# Sensors.net
KiCad netlist of a schematic drawn in Altium Designer
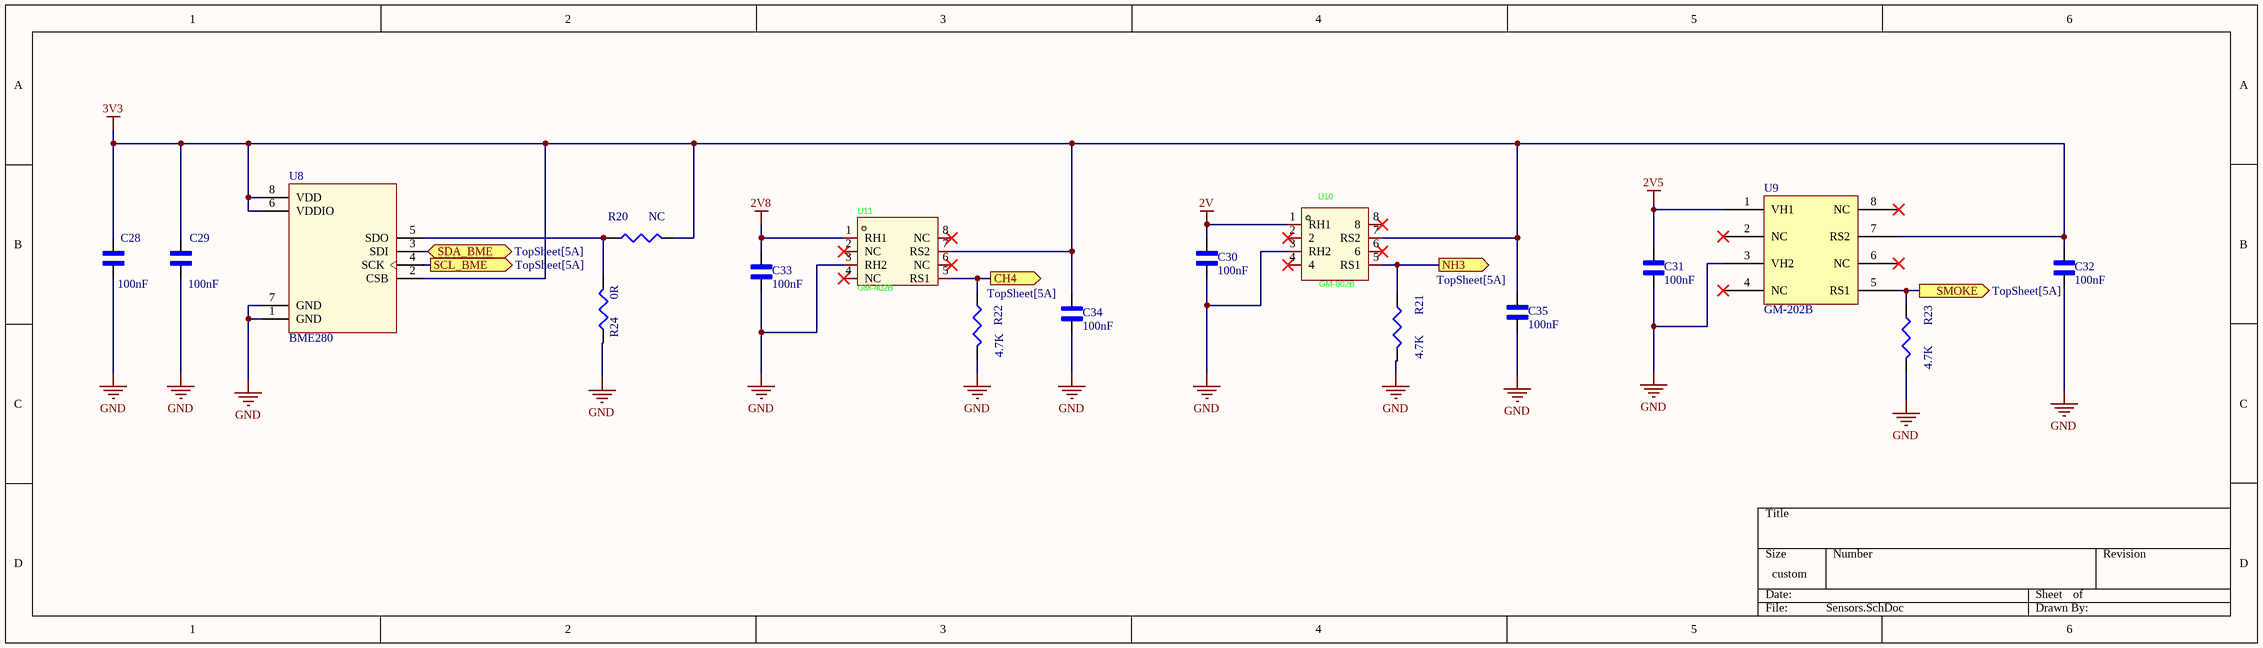
[diagram p0: Sensors.SchDoc]

(export (version "E")
  (design (tool "Eeschema 10.0.6"))
  (components
    (comp (ref "C28")
      (value "100nF")
      (footprint "C0603")
      (fields (field (name "MF") "Murata") (field (name "MP") "GJM1555C1HR10BB01J"))
      (libsource (lib "common component") (part "Capacitor non polar"))
    )
    (comp (ref "C29")
      (value "100nF")
      (footprint "C0603")
      (fields (field (name "MF") "Murata") (field (name "MP") "GJM1555C1HR10BB01J"))
      (libsource (lib "common component") (part "Capacitor non polar"))
    )
    (comp (ref "C30")
      (value "100nF")
      (footprint "C0603")
      (fields (field (name "MF") "Murata") (field (name "MP") "GJM1555C1HR10BB01J"))
      (libsource (lib "common component") (part "Capacitor non polar"))
    )
    (comp (ref "C31")
      (value "100nF")
      (footprint "C0603")
      (fields (field (name "MF") "Murata") (field (name "MP") "GJM1555C1HR10BB01J"))
      (libsource (lib "common component") (part "Capacitor non polar"))
    )
    (comp (ref "C32")
      (value "100nF")
      (footprint "C0603")
      (fields (field (name "MF") "Murata") (field (name "MP") "GJM1555C1HR10BB01J"))
      (libsource (lib "common component") (part "Capacitor non polar"))
    )
    (comp (ref "C33")
      (value "100nF")
      (footprint "C0603")
      (fields (field (name "MF") "Murata") (field (name "MP") "GJM1555C1HR10BB01J"))
      (libsource (lib "common component") (part "Capacitor non polar"))
    )
    (comp (ref "C34")
      (value "100nF")
      (footprint "C0603")
      (fields (field (name "MF") "Murata") (field (name "MP") "GJM1555C1HR10BB01J"))
      (libsource (lib "common component") (part "Capacitor non polar"))
    )
    (comp (ref "C35")
      (value "100nF")
      (footprint "C0603")
      (fields (field (name "MF") "Murata") (field (name "MP") "GJM1555C1HR10BB01J"))
      (libsource (lib "common component") (part "Capacitor non polar"))
    )
    (comp (ref "R20") (value "NC") (footprint "R0603") (libsource (lib "common component") (part "Resistor")))
    (comp (ref "R21")
      (value "4.7K")
      (footprint "R0603")
      (libsource (lib "common component") (part "Resistor"))
    )
    (comp (ref "R22")
      (value "4.7K")
      (footprint "R0603")
      (libsource (lib "common component") (part "Resistor"))
    )
    (comp (ref "R23")
      (value "4.7K")
      (footprint "R0603")
      (libsource (lib "common component") (part "Resistor"))
    )
    (comp (ref "R24") (value "0R") (footprint "R0603") (libsource (lib "common component") (part "Resistor")))
    (comp (ref "U8")
      (value "BME280")
      (footprint "PSON65P250X250X100-8N")
      (libsource (lib "BME280") (part "BME280"))
    )
    (comp (ref "U9")
      (value "GM-202B")
      (footprint "LCC-8_L5.0-W5.0-P1.27-BL")
      (description "Smoke Sensor winson")
      (libsource (lib "GM-202B") (part "GM-202B"))
    )
    (comp (ref "U10")
      (value "GM-802B")
      (footprint "LCC-8_L5.0-W5.0-P1.27-BL")
      (libsource (lib "GM-802B NH3 Sensor") (part "GM-802B_1"))
    )
    (comp (ref "U11")
      (value "GM-402B")
      (footprint "SENSORS-SMD_GM-402B")
      (fields (field (name "MANUFACTURER") "Winsen(炜盛)"))
      (libsource (lib "GM-402B") (part "GM-402B"))
    )
  )
  (nets
    (net (code "1") (name "/CH4") (class "Default")
      (node (ref "R22") (pin "1") (pinfunction "1_1") (pintype "passive"))
      (node (ref "U11") (pin "5") (pinfunction "RS1_5") (pintype "passive"))
    )
    (net (code "2") (name "/NH3") (class "Default")
      (node (ref "R21") (pin "1") (pinfunction "1_1") (pintype "passive"))
      (node (ref "U10") (pin "5") (pinfunction "RS1_5") (pintype "passive"))
    )
    (net (code "3") (name "/SCL_BME") (class "Default")
      (node (ref "U8") (pin "4") (pinfunction "SCK_4") (pintype "passive"))
    )
    (net (code "4") (name "/SDA_BME") (class "Default")
      (node (ref "U8") (pin "3") (pinfunction "SDI_3") (pintype "passive"))
    )
    (net (code "5") (name "/SMOKE") (class "Default")
      (node (ref "R23") (pin "1") (pinfunction "1_1") (pintype "passive"))
      (node (ref "U9") (pin "5") (pinfunction "RS1_5") (pintype "passive"))
    )
    (net (code "6") (name "2V") (class "Default")
      (node (ref "C30") (pin "2") (pinfunction "2_2") (pintype "passive"))
      (node (ref "U10") (pin "1") (pinfunction "RH1_1") (pintype "passive"))
    )
    (net (code "7") (name "2V5") (class "Default")
      (node (ref "C31") (pin "2") (pinfunction "2_2") (pintype "passive"))
      (node (ref "U9") (pin "1") (pinfunction "VH1_1") (pintype "passive"))
    )
    (net (code "8") (name "2V8") (class "Default")
      (node (ref "C33") (pin "2") (pinfunction "2_2") (pintype "passive"))
      (node (ref "U11") (pin "1") (pinfunction "RH1_1") (pintype "passive"))
    )
    (net (code "9") (name "3V3") (class "Default")
      (node (ref "C28") (pin "2") (pinfunction "2_2") (pintype "passive"))
      (node (ref "C29") (pin "2") (pinfunction "2_2") (pintype "passive"))
      (node (ref "C32") (pin "2") (pinfunction "2_2") (pintype "passive"))
      (node (ref "C34") (pin "2") (pinfunction "2_2") (pintype "passive"))
      (node (ref "C35") (pin "2") (pinfunction "2_2") (pintype "passive"))
      (node (ref "R20") (pin "2") (pinfunction "2_2") (pintype "passive"))
      (node (ref "U10") (pin "7") (pinfunction "RS2_7") (pintype "passive"))
      (node (ref "U11") (pin "7") (pinfunction "RS2_7") (pintype "passive"))
      (node (ref "U8") (pin "2") (pinfunction "CSB_2") (pintype "passive"))
      (node (ref "U8") (pin "6") (pinfunction "VDDIO_6") (pintype "power_in"))
      (node (ref "U8") (pin "8") (pinfunction "VDD_8") (pintype "power_in"))
      (node (ref "U9") (pin "7") (pinfunction "RS2_7") (pintype "passive"))
    )
    (net (code "10") (name "GND") (class "Default")
      (node (ref "C28") (pin "1") (pinfunction "1_1") (pintype "passive"))
      (node (ref "C29") (pin "1") (pinfunction "1_1") (pintype "passive"))
      (node (ref "C30") (pin "1") (pinfunction "1_1") (pintype "passive"))
      (node (ref "C31") (pin "1") (pinfunction "1_1") (pintype "passive"))
      (node (ref "C32") (pin "1") (pinfunction "1_1") (pintype "passive"))
      (node (ref "C33") (pin "1") (pinfunction "1_1") (pintype "passive"))
      (node (ref "C34") (pin "1") (pinfunction "1_1") (pintype "passive"))
      (node (ref "C35") (pin "1") (pinfunction "1_1") (pintype "passive"))
      (node (ref "R21") (pin "2") (pinfunction "2_2") (pintype "passive"))
      (node (ref "R22") (pin "2") (pinfunction "2_2") (pintype "passive"))
      (node (ref "R23") (pin "2") (pinfunction "2_2") (pintype "passive"))
      (node (ref "R24") (pin "1") (pinfunction "1_1") (pintype "passive"))
      (node (ref "U10") (pin "3") (pinfunction "RH2_3") (pintype "passive"))
      (node (ref "U11") (pin "3") (pinfunction "RH2_3") (pintype "passive"))
      (node (ref "U8") (pin "1") (pinfunction "GND_1") (pintype "power_in"))
      (node (ref "U8") (pin "7") (pinfunction "GND_7") (pintype "power_in"))
      (node (ref "U9") (pin "3") (pinfunction "VH2_3") (pintype "passive"))
    )
    (net (code "11") (name "Net-(U8-SDO)") (class "Default")
      (node (ref "R20") (pin "1") (pinfunction "1_1") (pintype "passive"))
      (node (ref "R24") (pin "2") (pinfunction "2_2") (pintype "passive"))
      (node (ref "U8") (pin "5") (pinfunction "SDO_5") (pintype "passive"))
    )
    (net (code "12") (name "unconnected-(U9-NC-Pad2)") (class "Default")
      (node (ref "U9") (pin "2") (pinfunction "NC_2") (pintype "passive+no_connect"))
    )
    (net (code "13") (name "unconnected-(U9-NC-Pad4)") (class "Default")
      (node (ref "U9") (pin "4") (pinfunction "NC_4") (pintype "passive+no_connect"))
    )
    (net (code "14") (name "unconnected-(U9-NC-Pad6)") (class "Default")
      (node (ref "U9") (pin "6") (pinfunction "NC_6") (pintype "passive+no_connect"))
    )
    (net (code "15") (name "unconnected-(U9-NC-Pad8)") (class "Default")
      (node (ref "U9") (pin "8") (pinfunction "NC_8") (pintype "passive+no_connect"))
    )
    (net (code "16") (name "unconnected-(U10-Pad2)") (class "Default")
      (node (ref "U10") (pin "2") (pinfunction "2_2") (pintype "passive+no_connect"))
    )
    (net (code "17") (name "unconnected-(U10-Pad4)") (class "Default")
      (node (ref "U10") (pin "4") (pinfunction "4_4") (pintype "passive+no_connect"))
    )
    (net (code "18") (name "unconnected-(U10-Pad6)") (class "Default")
      (node (ref "U10") (pin "6") (pinfunction "6_6") (pintype "passive+no_connect"))
    )
    (net (code "19") (name "unconnected-(U10-Pad8)") (class "Default")
      (node (ref "U10") (pin "8") (pinfunction "8_8") (pintype "passive+no_connect"))
    )
    (net (code "20") (name "unconnected-(U11-NC-Pad2)") (class "Default")
      (node (ref "U11") (pin "2") (pinfunction "NC_2") (pintype "passive+no_connect"))
    )
    (net (code "21") (name "unconnected-(U11-NC-Pad4)") (class "Default")
      (node (ref "U11") (pin "4") (pinfunction "NC_4") (pintype "passive+no_connect"))
    )
    (net (code "22") (name "unconnected-(U11-NC-Pad6)") (class "Default")
      (node (ref "U11") (pin "6") (pinfunction "NC_6") (pintype "passive+no_connect"))
    )
    (net (code "23") (name "unconnected-(U11-NC-Pad8)") (class "Default")
      (node (ref "U11") (pin "8") (pinfunction "NC_8") (pintype "passive+no_connect"))
    )
  )
)
